# schemat.net
KiCad netlist of a schematic drawn in EAGLE
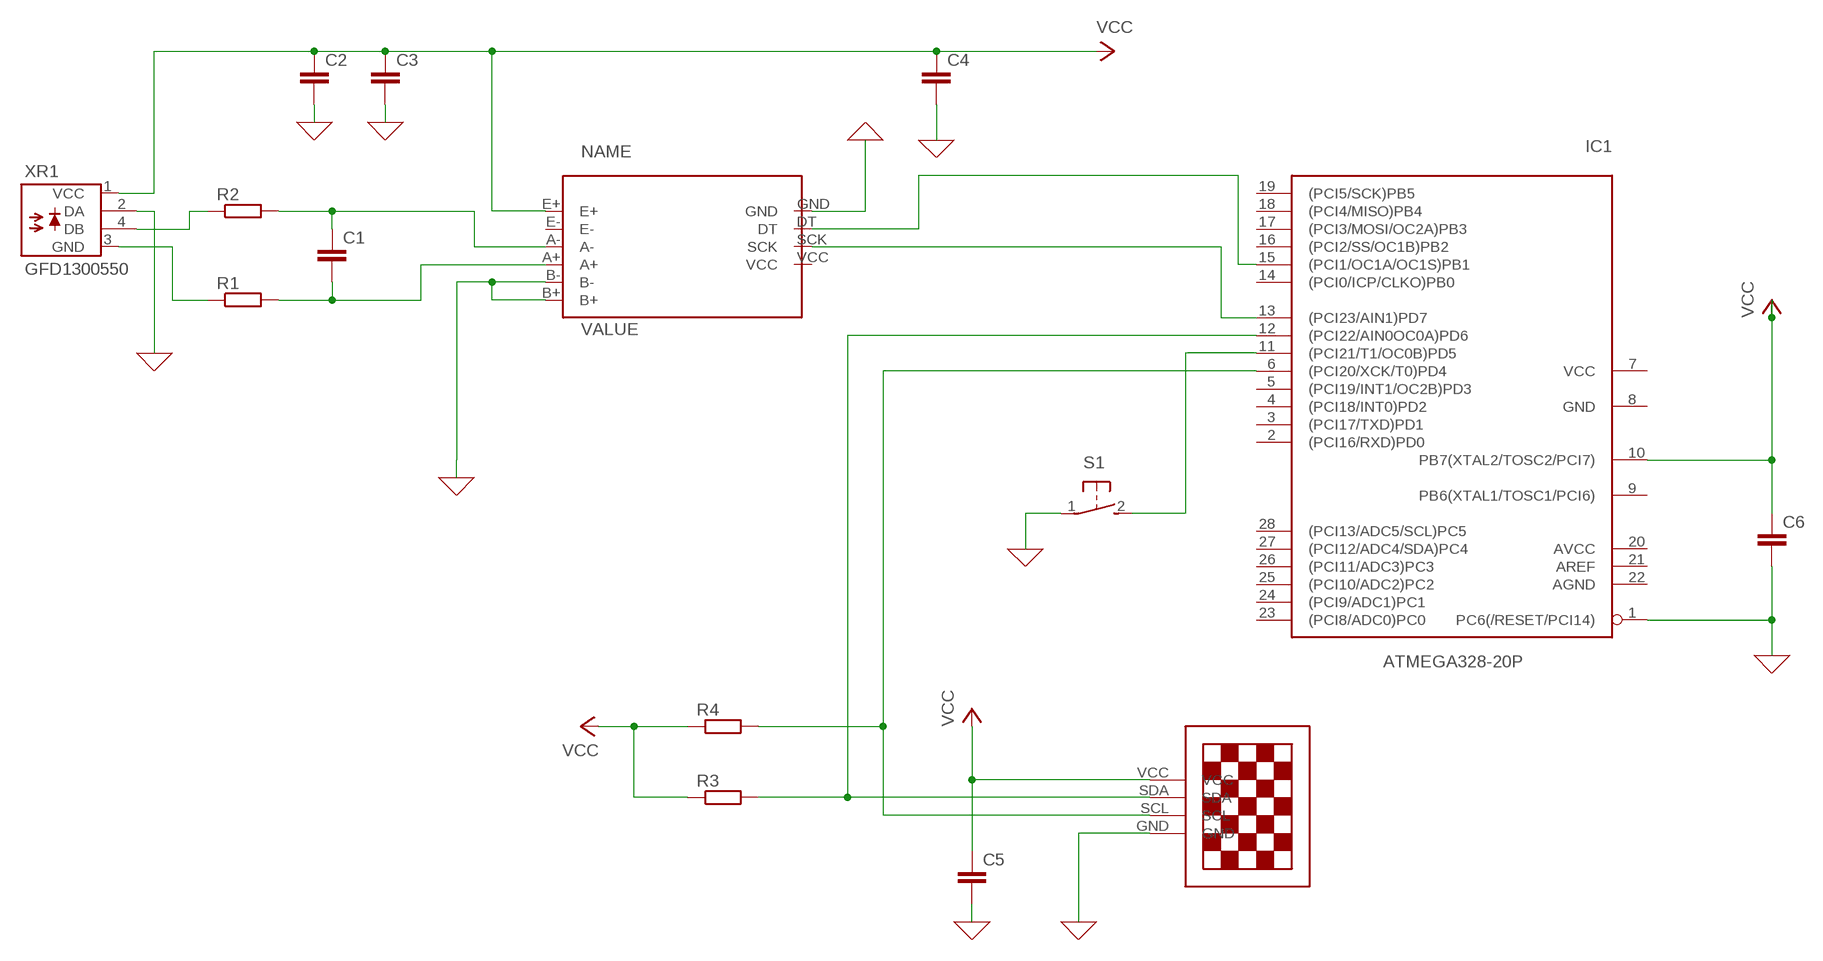
[diagram p0: schematic, sheet 1]

(export (version "E")
  (design (tool "Eeschema 10.0.6"))
  (components
    (comp (ref "C1")
      (value "C2,5-3")
      (footprint "eagle-import:C2.5-3")
      (libsource (lib "eagle-import") (part "C2,5-3"))
    )
    (comp (ref "C2")
      (value "C2,5-3")
      (footprint "eagle-import:C2.5-3")
      (libsource (lib "eagle-import") (part "C2,5-3"))
    )
    (comp (ref "C3")
      (value "C2,5-3")
      (footprint "eagle-import:C2.5-3")
      (libsource (lib "eagle-import") (part "C2,5-3"))
    )
    (comp (ref "C4")
      (value "C2,5-3")
      (footprint "eagle-import:C2.5-3")
      (libsource (lib "eagle-import") (part "C2,5-3"))
    )
    (comp (ref "C5")
      (value "C2,5-3")
      (footprint "eagle-import:C2.5-3")
      (libsource (lib "eagle-import") (part "C2,5-3"))
    )
    (comp (ref "C6")
      (value "C2,5-3")
      (footprint "eagle-import:C2.5-3")
      (libsource (lib "eagle-import") (part "C2,5-3"))
    )
    (comp (ref "IC1")
      (value "ATMEGA328-20P")
      (footprint "eagle-import:DIL28-3")
      (libsource (lib "eagle-import") (part "ATMEGA328P-20"))
    )
    (comp (ref "R1")
      (value "R-EU_0204/2V")
      (footprint "eagle-import:0204V")
      (libsource (lib "eagle-import") (part "R-EU_0204/2V"))
    )
    (comp (ref "R2")
      (value "R-EU_0204/2V")
      (footprint "eagle-import:0204V")
      (libsource (lib "eagle-import") (part "R-EU_0204/2V"))
    )
    (comp (ref "R3")
      (value "R-EU_0204/2V")
      (footprint "eagle-import:0204V")
      (libsource (lib "eagle-import") (part "R-EU_0204/2V"))
    )
    (comp (ref "R4")
      (value "R-EU_0204/2V")
      (footprint "eagle-import:0204V")
      (libsource (lib "eagle-import") (part "R-EU_0204/2V"))
    )
    (comp (ref "S1")
      (value "31-XX")
      (footprint "eagle-import:B3F-31XX")
      (fields (field (name "MPN") "B3F-3100"))
      (libsource (lib "eagle-import") (part "31-XX"))
    )
    (comp (ref "U$1")
      (value "HX711A")
      (footprint "eagle-import:HX711")
      (libsource (lib "eagle-import") (part "HX711A"))
    )
    (comp (ref "U$2")
      (value "13\"OLED13\"OLED")
      (footprint "eagle-import:1.3_OLED")
      (libsource (lib "eagle-import") (part "13{dblquote}OLED13{dblquote}OLED"))
    )
    (comp (ref "XR1")
      (value "GFD1300550")
      (footprint "eagle-import:GFD1300")
      (libsource (lib "eagle-import") (part "GFD1300550"))
    )
  )
  (nets
    (net (code "1") (name "GND") (class "Default")
      (node (ref "C2") (pin "2") (pinfunction "2_2") (pintype "passive"))
      (node (ref "C3") (pin "2") (pinfunction "2_2") (pintype "passive"))
      (node (ref "C4") (pin "2") (pinfunction "2_2") (pintype "passive"))
      (node (ref "C5") (pin "2") (pinfunction "2_2") (pintype "passive"))
      (node (ref "C6") (pin "2") (pinfunction "2_2") (pintype "passive"))
      (node (ref "IC1") (pin "1") (pinfunction "PC6(/RESET/PCI14)_1") (pintype "bidirectional"))
      (node (ref "S1") (pin "1") (pinfunction "P_1") (pintype "passive"))
      (node (ref "U$1") (pin "B+") (pinfunction "B+_B+") (pintype "bidirectional"))
      (node (ref "U$1") (pin "B-") (pinfunction "B-_B-") (pintype "bidirectional"))
      (node (ref "U$1") (pin "GND") (pinfunction "GND_GND") (pintype "bidirectional"))
      (node (ref "U$2") (pin "GND") (pinfunction "GND_GND") (pintype "bidirectional"))
      (node (ref "XR1") (pin "2") (pinfunction "DA_2") (pintype "output"))
    )
    (net (code "2") (name "Net-(C1-Pad1)") (class "Default")
      (node (ref "C1") (pin "1") (pinfunction "1_1") (pintype "passive"))
      (node (ref "R2") (pin "2") (pinfunction "2_2") (pintype "passive"))
      (node (ref "U$1") (pin "A-") (pinfunction "A-_A-") (pintype "bidirectional"))
    )
    (net (code "3") (name "Net-(C1-Pad2)") (class "Default")
      (node (ref "C1") (pin "2") (pinfunction "2_2") (pintype "passive"))
      (node (ref "R1") (pin "2") (pinfunction "2_2") (pintype "passive"))
      (node (ref "U$1") (pin "A+") (pinfunction "A+_A+") (pintype "bidirectional"))
    )
    (net (code "4") (name "Net-(IC1-(PCI1{slash}OC1A{slash}OC1S)PB1)") (class "Default")
      (node (ref "IC1") (pin "15") (pinfunction "(PCI1/OC1A/OC1S)PB1_15") (pintype "bidirectional"))
      (node (ref "U$1") (pin "DT") (pinfunction "DT_DT") (pintype "bidirectional"))
    )
    (net (code "5") (name "Net-(IC1-(PCI20{slash}XCK{slash}T0)PD4)") (class "Default")
      (node (ref "IC1") (pin "6") (pinfunction "(PCI20/XCK/T0)PD4_6") (pintype "bidirectional"))
      (node (ref "R4") (pin "2") (pinfunction "2_2") (pintype "passive"))
      (node (ref "U$2") (pin "SCL") (pinfunction "SCL_SCL") (pintype "bidirectional"))
    )
    (net (code "6") (name "Net-(IC1-(PCI21{slash}T1{slash}OC0B)PD5)") (class "Default")
      (node (ref "IC1") (pin "11") (pinfunction "(PCI21/T1/OC0B)PD5_11") (pintype "bidirectional"))
      (node (ref "S1") (pin "2") (pinfunction "S_2") (pintype "passive"))
    )
    (net (code "7") (name "Net-(IC1-(PCI22{slash}AIN0OC0A)PD6)") (class "Default")
      (node (ref "IC1") (pin "12") (pinfunction "(PCI22/AIN0OC0A)PD6_12") (pintype "bidirectional"))
      (node (ref "R3") (pin "2") (pinfunction "2_2") (pintype "passive"))
      (node (ref "U$2") (pin "SDA") (pinfunction "SDA_SDA") (pintype "bidirectional"))
    )
    (net (code "8") (name "Net-(IC1-(PCI23{slash}AIN1)PD7)") (class "Default")
      (node (ref "IC1") (pin "13") (pinfunction "(PCI23/AIN1)PD7_13") (pintype "bidirectional"))
      (node (ref "U$1") (pin "SCK") (pinfunction "SCK_SCK") (pintype "bidirectional"))
    )
    (net (code "9") (name "Net-(XR1-DB)") (class "Default")
      (node (ref "R2") (pin "1") (pinfunction "1_1") (pintype "passive"))
      (node (ref "XR1") (pin "4") (pinfunction "DB_4") (pintype "output"))
    )
    (net (code "10") (name "Net-(XR1-GND)") (class "Default")
      (node (ref "R1") (pin "1") (pinfunction "1_1") (pintype "passive"))
      (node (ref "XR1") (pin "3") (pinfunction "GND_3") (pintype "power_in"))
    )
    (net (code "11") (name "VCC") (class "Default")
      (node (ref "C2") (pin "1") (pinfunction "1_1") (pintype "passive"))
      (node (ref "C3") (pin "1") (pinfunction "1_1") (pintype "passive"))
      (node (ref "C4") (pin "1") (pinfunction "1_1") (pintype "passive"))
      (node (ref "C5") (pin "1") (pinfunction "1_1") (pintype "passive"))
      (node (ref "C6") (pin "1") (pinfunction "1_1") (pintype "passive"))
      (node (ref "IC1") (pin "10") (pinfunction "PB7(XTAL2/TOSC2/PCI7)_10") (pintype "bidirectional"))
      (node (ref "R3") (pin "1") (pinfunction "1_1") (pintype "passive"))
      (node (ref "R4") (pin "1") (pinfunction "1_1") (pintype "passive"))
      (node (ref "U$1") (pin "E+") (pinfunction "E+_E+") (pintype "bidirectional"))
      (node (ref "U$2") (pin "VCC") (pinfunction "VCC_VCC") (pintype "bidirectional"))
      (node (ref "XR1") (pin "1") (pinfunction "VCC_1") (pintype "power_in"))
    )
    (net (code "12") (name "unconnected-(IC1-(PCI0{slash}ICP{slash}CLKO)PB0-Pad14)") (class "Default")
      (node (ref "IC1") (pin "14") (pinfunction "(PCI0/ICP/CLKO)PB0_14") (pintype "bidirectional"))
    )
    (net (code "13") (name "unconnected-(IC1-(PCI2{slash}SS{slash}OC1B)PB2-Pad16)") (class "Default")
      (node (ref "IC1") (pin "16") (pinfunction "(PCI2/SS/OC1B)PB2_16") (pintype "bidirectional"))
    )
    (net (code "14") (name "unconnected-(IC1-(PCI3{slash}MOSI{slash}OC2A)PB3-Pad17)") (class "Default")
      (node (ref "IC1") (pin "17") (pinfunction "(PCI3/MOSI/OC2A)PB3_17") (pintype "bidirectional"))
    )
    (net (code "15") (name "unconnected-(IC1-(PCI4{slash}MISO)PB4-Pad18)") (class "Default")
      (node (ref "IC1") (pin "18") (pinfunction "(PCI4/MISO)PB4_18") (pintype "bidirectional"))
    )
    (net (code "16") (name "unconnected-(IC1-(PCI5{slash}SCK)PB5-Pad19)") (class "Default")
      (node (ref "IC1") (pin "19") (pinfunction "(PCI5/SCK)PB5_19") (pintype "bidirectional"))
    )
    (net (code "17") (name "unconnected-(IC1-(PCI8{slash}ADC0)PC0-Pad23)") (class "Default")
      (node (ref "IC1") (pin "23") (pinfunction "(PCI8/ADC0)PC0_23") (pintype "bidirectional"))
    )
    (net (code "18") (name "unconnected-(IC1-(PCI9{slash}ADC1)PC1-Pad24)") (class "Default")
      (node (ref "IC1") (pin "24") (pinfunction "(PCI9/ADC1)PC1_24") (pintype "bidirectional"))
    )
    (net (code "19") (name "unconnected-(IC1-(PCI10{slash}ADC2)PC2-Pad25)") (class "Default")
      (node (ref "IC1") (pin "25") (pinfunction "(PCI10/ADC2)PC2_25") (pintype "bidirectional"))
    )
    (net (code "20") (name "unconnected-(IC1-(PCI11{slash}ADC3)PC3-Pad26)") (class "Default")
      (node (ref "IC1") (pin "26") (pinfunction "(PCI11/ADC3)PC3_26") (pintype "bidirectional"))
    )
    (net (code "21") (name "unconnected-(IC1-(PCI12{slash}ADC4{slash}SDA)PC4-Pad27)") (class "Default")
      (node (ref "IC1") (pin "27") (pinfunction "(PCI12/ADC4/SDA)PC4_27") (pintype "bidirectional"))
    )
    (net (code "22") (name "unconnected-(IC1-(PCI13{slash}ADC5{slash}SCL)PC5-Pad28)") (class "Default")
      (node (ref "IC1") (pin "28") (pinfunction "(PCI13/ADC5/SCL)PC5_28") (pintype "bidirectional"))
    )
    (net (code "23") (name "unconnected-(IC1-(PCI16{slash}RXD)PD0-Pad2)") (class "Default")
      (node (ref "IC1") (pin "2") (pinfunction "(PCI16/RXD)PD0_2") (pintype "bidirectional"))
    )
    (net (code "24") (name "unconnected-(IC1-(PCI17{slash}TXD)PD1-Pad3)") (class "Default")
      (node (ref "IC1") (pin "3") (pinfunction "(PCI17/TXD)PD1_3") (pintype "bidirectional"))
    )
    (net (code "25") (name "unconnected-(IC1-(PCI18{slash}INT0)PD2-Pad4)") (class "Default")
      (node (ref "IC1") (pin "4") (pinfunction "(PCI18/INT0)PD2_4") (pintype "bidirectional"))
    )
    (net (code "26") (name "unconnected-(IC1-(PCI19{slash}INT1{slash}OC2B)PD3-Pad5)") (class "Default")
      (node (ref "IC1") (pin "5") (pinfunction "(PCI19/INT1/OC2B)PD3_5") (pintype "bidirectional"))
    )
    (net (code "27") (name "unconnected-(IC1-AGND-Pad22)") (class "Default")
      (node (ref "IC1") (pin "22") (pinfunction "AGND_22") (pintype "bidirectional"))
    )
    (net (code "28") (name "unconnected-(IC1-AREF-Pad21)") (class "Default")
      (node (ref "IC1") (pin "21") (pinfunction "AREF_21") (pintype "bidirectional"))
    )
    (net (code "29") (name "unconnected-(IC1-AVCC-Pad20)") (class "Default")
      (node (ref "IC1") (pin "20") (pinfunction "AVCC_20") (pintype "bidirectional"))
    )
    (net (code "30") (name "unconnected-(IC1-GND-Pad8)") (class "Default")
      (node (ref "IC1") (pin "8") (pinfunction "GND_8") (pintype "bidirectional"))
    )
    (net (code "31") (name "unconnected-(IC1-PB6(XTAL1{slash}TOSC1{slash}PCI6)-Pad9)") (class "Default")
      (node (ref "IC1") (pin "9") (pinfunction "PB6(XTAL1/TOSC1/PCI6)_9") (pintype "bidirectional"))
    )
    (net (code "32") (name "unconnected-(IC1-VCC-Pad7)") (class "Default")
      (node (ref "IC1") (pin "7") (pinfunction "VCC_7") (pintype "bidirectional"))
    )
    (net (code "33") (name "unconnected-(U$1-PadE-)") (class "Default")
      (node (ref "U$1") (pin "E-") (pinfunction "E-_E-") (pintype "bidirectional"))
    )
    (net (code "34") (name "unconnected-(U$1-PadVCC)") (class "Default")
      (node (ref "U$1") (pin "VCC") (pinfunction "VCC_VCC") (pintype "bidirectional"))
    )
  )
)
